# FPGA_CLKs.net
KiCad netlist of a schematic drawn in Altium Designer
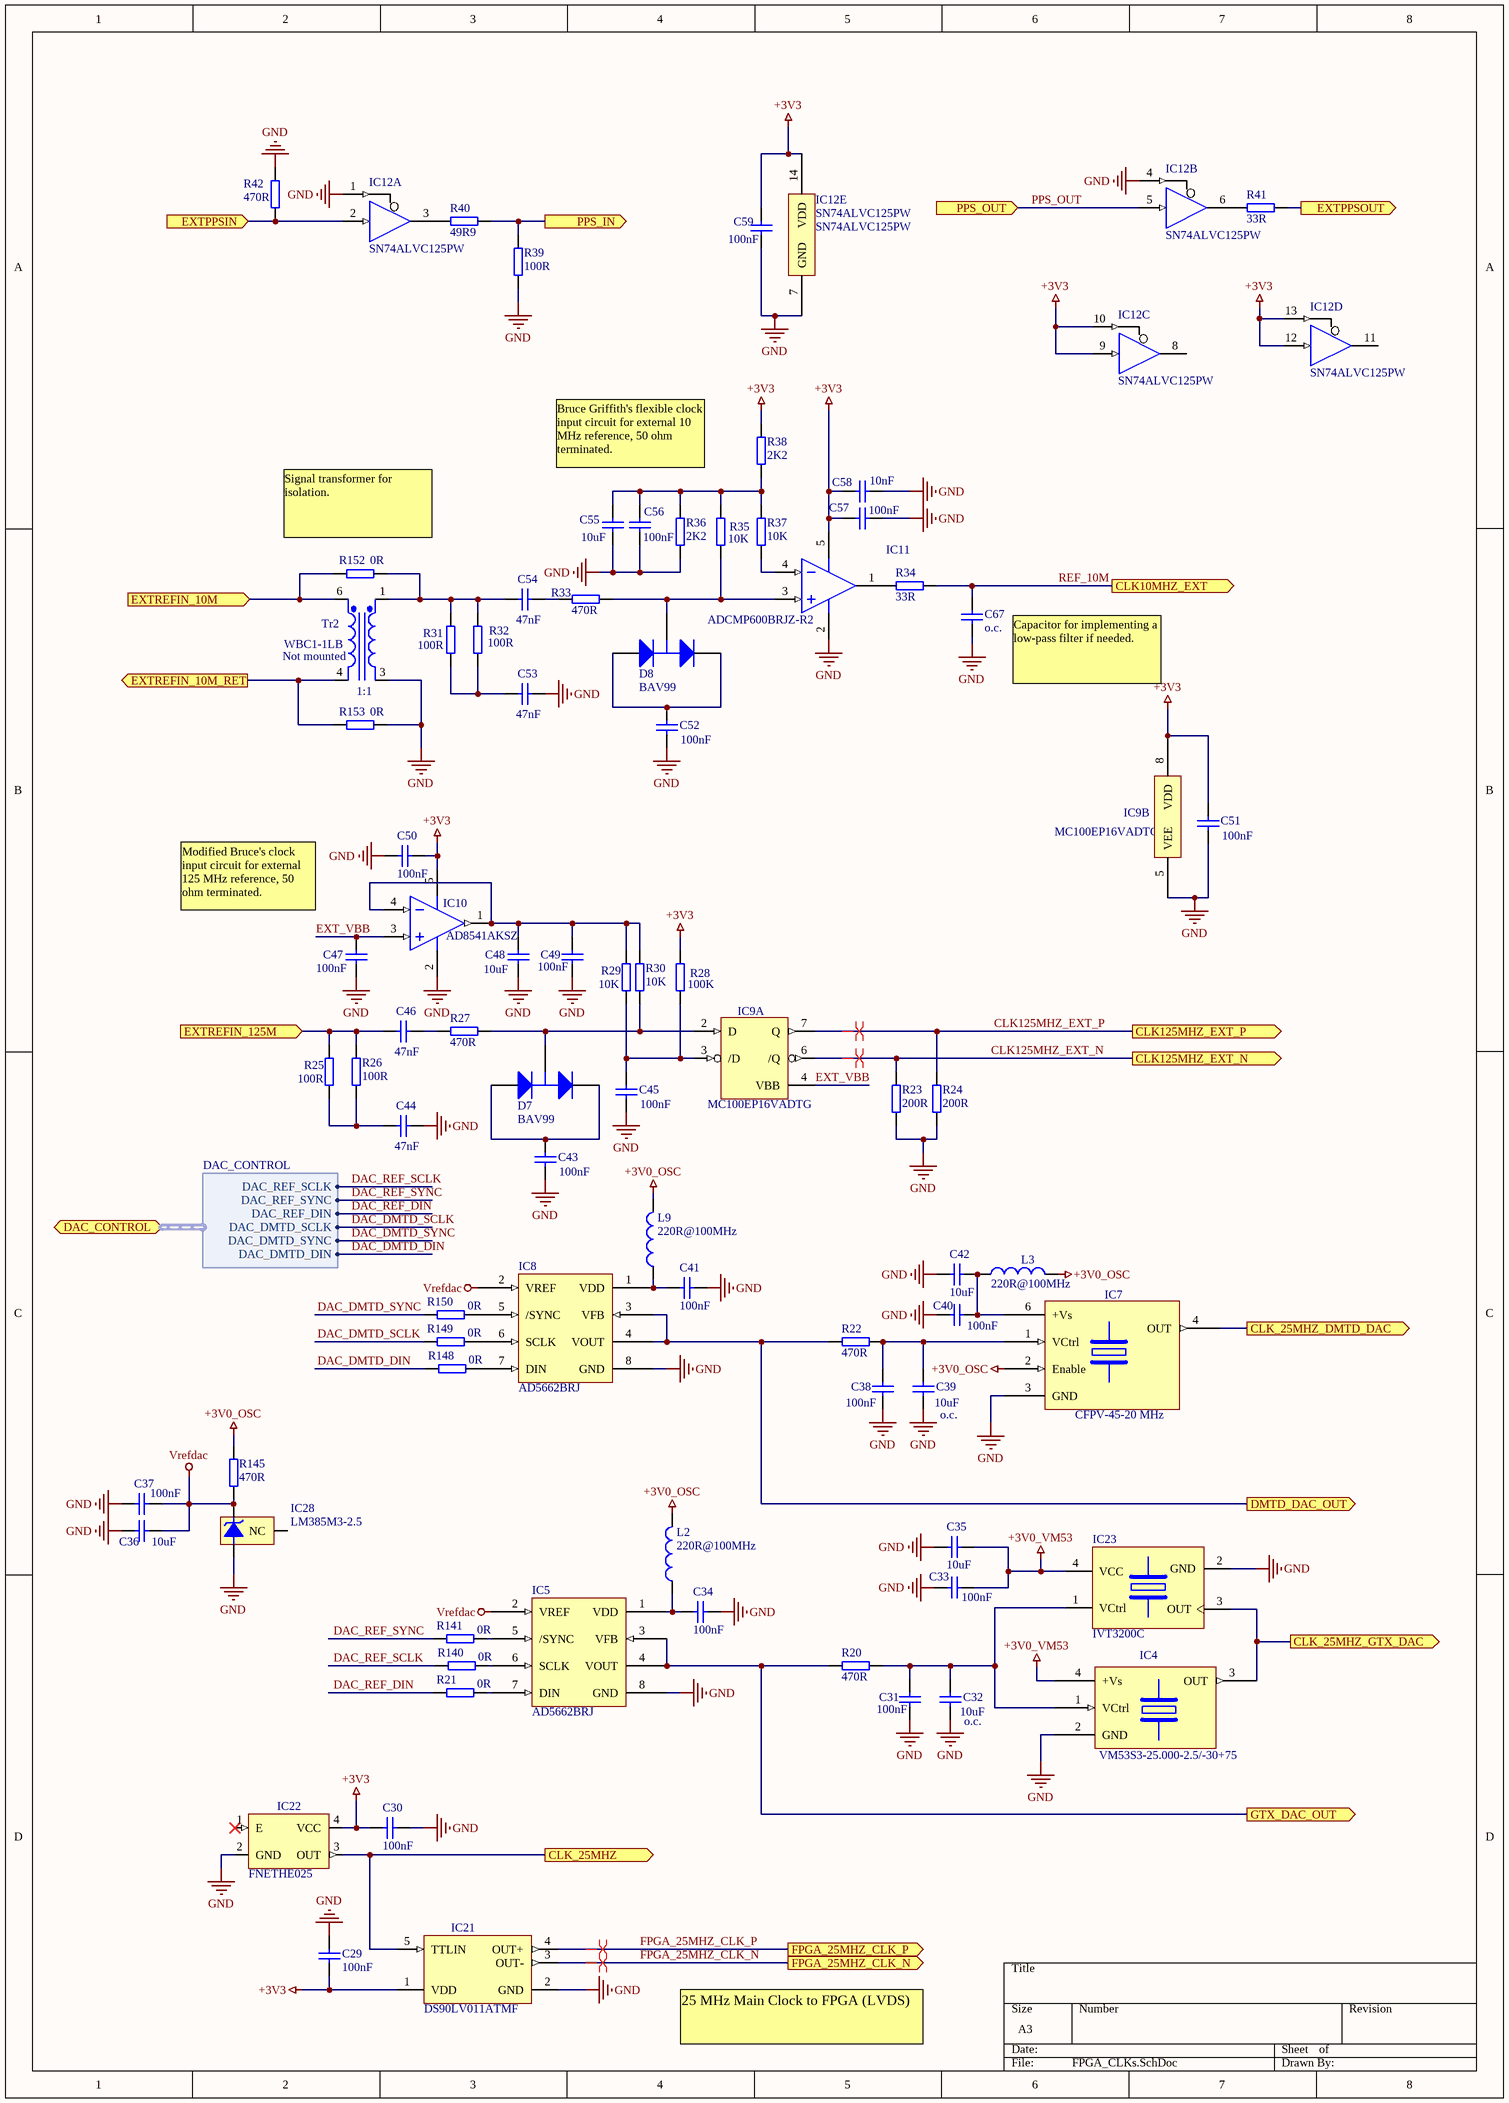
[diagram p0: FPGA_CLKs.SchDoc]

(export (version "E")
  (design (tool "Eeschema 10.0.6"))
  (components
    (comp (ref "C29")
      (value "100nF")
      (footprint "CC1005-0402")
      (description "Capacitor")
      (fields
        (field (name "TOLERANCE") "±10%")
        (field (name "VOLTAGE") "16V")
        (field (name "PUBLISHER") "Altium Limited")
      )
      (libsource (lib "wr_switch") (part "Cap"))
    )
    (comp (ref "C30")
      (value "100nF")
      (footprint "CC1005-0402")
      (description "Capacitor")
      (fields
        (field (name "TOLERANCE") "±10%")
        (field (name "VOLTAGE") "16V")
        (field (name "PUBLISHER") "Altium Limited")
      )
      (libsource (lib "wr_switch") (part "Cap"))
    )
    (comp (ref "C31")
      (value "100nF")
      (footprint "CC1005-0402")
      (description "Capacitor")
      (fields
        (field (name "TOLERANCE") "±10%")
        (field (name "VOLTAGE") "16V")
        (field (name "PUBLISHER") "Altium Limited")
      )
      (libsource (lib "wr_switch") (part "Cap"))
    )
    (comp (ref "C32")
      (value "10uF")
      (footprint "CC1608-0603")
      (description "Capacitor")
      (fields
        (field (name "TOLERANCE") "±20%")
        (field (name "VOLTAGE") "6.3V")
        (field (name "ALTIUM_VALUE") "o.c.")
        (field (name "PUBLISHER") "Altium Limited")
      )
      (libsource (lib "wr_switch") (part "Cap"))
    )
    (comp (ref "C33")
      (value "100nF")
      (footprint "CC1005-0402")
      (description "Capacitor")
      (fields
        (field (name "TOLERANCE") "±10%")
        (field (name "VOLTAGE") "16V")
        (field (name "PUBLISHER") "Altium Limited")
      )
      (libsource (lib "wr_switch") (part "Cap"))
    )
    (comp (ref "C34")
      (value "100nF")
      (footprint "CC1005-0402")
      (description "Capacitor")
      (fields
        (field (name "TOLERANCE") "±10%")
        (field (name "VOLTAGE") "16V")
        (field (name "PUBLISHER") "Altium Limited")
      )
      (libsource (lib "wr_switch") (part "Cap"))
    )
    (comp (ref "C35")
      (value "10uF")
      (footprint "CC1608-0603")
      (description "Capacitor")
      (fields
        (field (name "TOLERANCE") "±20%")
        (field (name "VOLTAGE") "6.3V")
        (field (name "PUBLISHER") "Altium Limited")
      )
      (libsource (lib "wr_switch") (part "Cap"))
    )
    (comp (ref "C36")
      (value "10uF")
      (footprint "CC1608-0603")
      (description "Capacitor")
      (fields
        (field (name "TOLERANCE") "±20%")
        (field (name "VOLTAGE") "6.3V")
        (field (name "PUBLISHER") "Altium Limited")
      )
      (libsource (lib "wr_switch") (part "Cap"))
    )
    (comp (ref "C37")
      (value "100nF")
      (footprint "CC1005-0402")
      (description "Capacitor")
      (fields
        (field (name "TOLERANCE") "±10%")
        (field (name "VOLTAGE") "16V")
        (field (name "PUBLISHER") "Altium Limited")
      )
      (libsource (lib "wr_switch") (part "Cap"))
    )
    (comp (ref "C38")
      (value "100nF")
      (footprint "CC1005-0402")
      (description "Capacitor")
      (fields
        (field (name "TOLERANCE") "±10%")
        (field (name "VOLTAGE") "16V")
        (field (name "PUBLISHER") "Altium Limited")
      )
      (libsource (lib "wr_switch") (part "Cap"))
    )
    (comp (ref "C39")
      (value "10uF")
      (footprint "CC1608-0603")
      (description "Capacitor")
      (fields
        (field (name "TOLERANCE") "±20%")
        (field (name "VOLTAGE") "6.3V")
        (field (name "ALTIUM_VALUE") "o.c.")
        (field (name "PUBLISHER") "Altium Limited")
      )
      (libsource (lib "wr_switch") (part "Cap"))
    )
    (comp (ref "C40")
      (value "100nF")
      (footprint "CC1005-0402")
      (description "Capacitor")
      (fields
        (field (name "TOLERANCE") "±10%")
        (field (name "VOLTAGE") "16V")
        (field (name "PUBLISHER") "Altium Limited")
      )
      (libsource (lib "wr_switch") (part "Cap"))
    )
    (comp (ref "C41")
      (value "100nF")
      (footprint "CC1005-0402")
      (description "Capacitor")
      (fields
        (field (name "TOLERANCE") "±10%")
        (field (name "VOLTAGE") "16V")
        (field (name "PUBLISHER") "Altium Limited")
      )
      (libsource (lib "wr_switch") (part "Cap"))
    )
    (comp (ref "C42")
      (value "10uF")
      (footprint "CC1608-0603")
      (description "Capacitor")
      (fields
        (field (name "TOLERANCE") "±20%")
        (field (name "VOLTAGE") "6.3V")
        (field (name "PUBLISHER") "Altium Limited")
      )
      (libsource (lib "wr_switch") (part "Cap"))
    )
    (comp (ref "C43")
      (value "100nF")
      (footprint "CC1005-0402")
      (description "Capacitor")
      (fields
        (field (name "TOLERANCE") "±10%")
        (field (name "VOLTAGE") "16V")
        (field (name "PUBLISHER") "Altium Limited")
      )
      (libsource (lib "wr_switch") (part "Cap"))
    )
    (comp (ref "C44")
      (value "47nF")
      (footprint "CC1005-0402")
      (description "Capacitor")
      (fields
        (field (name "TOLERANCE") "±10%")
        (field (name "VOLTAGE") "25V")
        (field (name "PUBLISHER") "Altium Limited")
      )
      (libsource (lib "wr_switch") (part "Cap"))
    )
    (comp (ref "C45")
      (value "100nF")
      (footprint "CC1005-0402")
      (description "Capacitor")
      (fields
        (field (name "TOLERANCE") "±10%")
        (field (name "VOLTAGE") "16V")
        (field (name "PUBLISHER") "Altium Limited")
      )
      (libsource (lib "wr_switch") (part "Cap"))
    )
    (comp (ref "C46")
      (value "47nF")
      (footprint "CC1005-0402")
      (description "Capacitor")
      (fields
        (field (name "TOLERANCE") "±10%")
        (field (name "VOLTAGE") "25V")
        (field (name "PUBLISHER") "Altium Limited")
      )
      (libsource (lib "wr_switch") (part "Cap"))
    )
    (comp (ref "C47")
      (value "100nF")
      (footprint "CC1005-0402")
      (description "Capacitor")
      (fields
        (field (name "TOLERANCE") "±10%")
        (field (name "VOLTAGE") "16V")
        (field (name "PUBLISHER") "Altium Limited")
      )
      (libsource (lib "wr_switch") (part "Cap"))
    )
    (comp (ref "C48")
      (value "10uF")
      (footprint "CC1608-0603")
      (description "Capacitor")
      (fields
        (field (name "TOLERANCE") "±20%")
        (field (name "VOLTAGE") "6.3V")
        (field (name "PUBLISHER") "Altium Limited")
      )
      (libsource (lib "wr_switch") (part "Cap"))
    )
    (comp (ref "C49")
      (value "100nF")
      (footprint "CC1005-0402")
      (description "Capacitor")
      (fields
        (field (name "TOLERANCE") "±10%")
        (field (name "VOLTAGE") "16V")
        (field (name "PUBLISHER") "Altium Limited")
      )
      (libsource (lib "wr_switch") (part "Cap"))
    )
    (comp (ref "C50")
      (value "100nF")
      (footprint "CC1005-0402")
      (description "Capacitor")
      (fields
        (field (name "TOLERANCE") "±10%")
        (field (name "VOLTAGE") "16V")
        (field (name "PUBLISHER") "Altium Limited")
      )
      (libsource (lib "wr_switch") (part "Cap"))
    )
    (comp (ref "C51")
      (value "100nF")
      (footprint "CC1005-0402")
      (description "Capacitor")
      (fields
        (field (name "TOLERANCE") "±10%")
        (field (name "VOLTAGE") "16V")
        (field (name "PUBLISHER") "Altium Limited")
      )
      (libsource (lib "wr_switch") (part "Cap"))
    )
    (comp (ref "C52")
      (value "100nF")
      (footprint "CC1005-0402")
      (description "Capacitor")
      (fields
        (field (name "TOLERANCE") "±10%")
        (field (name "VOLTAGE") "16V")
        (field (name "PUBLISHER") "Altium Limited")
      )
      (libsource (lib "wr_switch") (part "Cap"))
    )
    (comp (ref "C53")
      (value "47nF")
      (footprint "CC1005-0402")
      (description "Capacitor")
      (fields
        (field (name "TOLERANCE") "±10%")
        (field (name "VOLTAGE") "25V")
        (field (name "PUBLISHER") "Altium Limited")
      )
      (libsource (lib "wr_switch") (part "Cap"))
    )
    (comp (ref "C54")
      (value "47nF")
      (footprint "CC1005-0402")
      (description "Capacitor")
      (fields
        (field (name "TOLERANCE") "±10%")
        (field (name "VOLTAGE") "25V")
        (field (name "PUBLISHER") "Altium Limited")
      )
      (libsource (lib "wr_switch") (part "Cap"))
    )
    (comp (ref "C55")
      (value "10uF")
      (footprint "CC1608-0603")
      (description "Capacitor")
      (fields
        (field (name "TOLERANCE") "±20%")
        (field (name "VOLTAGE") "6.3V")
        (field (name "PUBLISHER") "Altium Limited")
      )
      (libsource (lib "wr_switch") (part "Cap"))
    )
    (comp (ref "C56")
      (value "100nF")
      (footprint "CC1005-0402")
      (description "Capacitor")
      (fields
        (field (name "TOLERANCE") "±10%")
        (field (name "VOLTAGE") "16V")
        (field (name "PUBLISHER") "Altium Limited")
      )
      (libsource (lib "wr_switch") (part "Cap"))
    )
    (comp (ref "C57")
      (value "100nF")
      (footprint "CC1005-0402")
      (description "Capacitor")
      (fields
        (field (name "TOLERANCE") "±10%")
        (field (name "VOLTAGE") "16V")
        (field (name "PUBLISHER") "Altium Limited")
      )
      (libsource (lib "wr_switch") (part "Cap"))
    )
    (comp (ref "C58")
      (value "10nF")
      (footprint "CC1005-0402")
      (description "Capacitor")
      (fields
        (field (name "TOLERANCE") "±10%")
        (field (name "VOLTAGE") "25V")
        (field (name "PUBLISHER") "Altium Limited")
      )
      (libsource (lib "wr_switch") (part "Cap"))
    )
    (comp (ref "C59")
      (value "100nF")
      (footprint "CC1005-0402")
      (description "Capacitor")
      (fields
        (field (name "TOLERANCE") "±10%")
        (field (name "VOLTAGE") "16V")
        (field (name "PUBLISHER") "Altium Limited")
      )
      (libsource (lib "wr_switch") (part "Cap"))
    )
    (comp (ref "C67")
      (value "o.c.")
      (footprint "CC1608-0603")
      (description "Capacitor")
      (fields
        (field (name "TOLERANCE") "±10%")
        (field (name "VOLTAGE") "16V")
        (field (name "PUBLISHER") "Altium Limited")
      )
      (libsource (lib "wr_switch") (part "Cap"))
    )
    (comp (ref "D7")
      (value "BAV99")
      (footprint "SOT-23")
      (description "Silicon Switching Diode Array for High-Speed Switching")
      (fields (field (name "PUBLISHER") "Altium Limited"))
      (libsource (lib "Infineon Discrete Diode") (part "BAV99"))
    )
    (comp (ref "D8")
      (value "BAV99")
      (footprint "SOT-23")
      (description "Silicon Switching Diode Array for High-Speed Switching")
      (fields (field (name "PUBLISHER") "Altium Limited"))
      (libsource (lib "Infineon Discrete Diode") (part "BAV99"))
    )
    (comp (ref "IC4")
      (value "VM53S3-25.000-2.5/-30+75")
      (footprint "VCTCXO_VM53S")
      (description "VCTCXO oscillator")
      (libsource (lib "wr_switch") (part "VCTCXO_VM53S"))
    )
    (comp (ref "IC5")
      (value "AD5662BRJ")
      (footprint "SOT23-8")
      (description "Analog Devices 16-bit DAC w/SPI interface, ext ref")
      (fields (field (name "Comment") "AD5662B"))
      (libsource (lib "wr_switch") (part "AD5662"))
    )
    (comp (ref "IC7")
      (value "CFPV-45-20 MHz")
      (footprint "vs-705")
      (description "VCXO oscillator")
      (fields (field (name "MANUFACTURER") "IQD Frequency"))
      (libsource (lib "wr_switch") (part "VCXO_CFPV_45"))
    )
    (comp (ref "IC8")
      (value "AD5662BRJ")
      (footprint "SOT23-8")
      (description "Analog Devices 16-bit DAC w/SPI interface, ext ref")
      (fields (field (name "Comment") "AD5662B"))
      (libsource (lib "wr_switch") (part "AD5662"))
    )
    (comp (ref "IC9")
      (value "MC100EP16VADTG")
      (footprint "TSOP65P490-8AN")
      (description "ONSemi differental receiver w/ECL output")
      (fields (field (name "Comment") "MC100EP16"))
      (libsource (lib "wr_switch") (part "MC100EP16"))
    )
    (comp (ref "IC10")
      (value "AD8541AKSZ")
      (footprint "SOT65P210X110-5N")
      (description "Analog Devices general purpose low-voltage R2R CMOS opamp")
      (libsource (lib "wr_switch") (part "AD8541"))
    )
    (comp (ref "IC11")
      (value "ADCMP600BRJZ-R2")
      (footprint "SOT23-5AL")
      (description "Analog Devices fast comparator")
      (libsource (lib "wr_switch") (part "ADCMP600"))
    )
    (comp (ref "IC12")
      (value "SN74ALVC125PW")
      (footprint "PW014")
      (description "Quad Buffer with 3-State Outputs with TTL Compatible Inputs")
      (fields (field (name "ALTIUM_VALUE") "SN74ALVC125PW") (field (name "Comment") "SN74ALVC125"))
      (libsource (lib "wr_switch") (part "SN74ALVC125"))
    )
    (comp (ref "IC21")
      (value "DS90LV011ATMF")
      (footprint "MF05A_N")
      (description "Single High Speed Differential Driver")
      (fields
        (field (name "MANUFACTURER") "National Semiconductor")
        (field (name "DIGIKEYPARTNUMBER") "DS90LV011ATMFTR-ND")
        (field (name "PUBLISHER") "Altium Limited")
      )
      (libsource (lib "NSC Interface") (part "DS90LV011ATMF"))
    )
    (comp (ref "IC22")
      (value "FNETHE025")
      (footprint "SPXO")
      (description "SMD oscillator 3.3V (Elfa)")
      (libsource (lib "wr_switch") (part "OSC_CFPS-73"))
    )
    (comp (ref "IC23")
      (value "IVT3200C")
      (footprint "OSC_RAKON_IVT3200C")
      (libsource (lib "wr_switch") (part "IVT32000C"))
    )
    (comp (ref "IC28")
      (value "LM385M3-2.5")
      (footprint "MF03A_N")
      (description "Micropower Voltage Reference Diode")
      (fields
        (field (name "MANUFACTURER") "National Semiconductor")
        (field (name "DIGIKEYPARTNUMBER") "LM385M3-2.5CT-ND")
        (field (name "PUBLISHER") "Altium Limited")
      )
      (libsource (lib "NSC Voltage Reference") (part "LM385M3-2.5"))
    )
    (comp (ref "L2")
      (value "220R@100MHz Ferrite Bead")
      (footprint "0603")
      (description "ferrite bead")
      (fields (field (name "IMPEDANCE") "220R@100MHz"))
      (libsource (lib "wr_switch") (part "L_FERRITE_BEAD"))
    )
    (comp (ref "L3")
      (value "220R@100MHz Ferrite Bead")
      (footprint "0603")
      (description "ferrite bead")
      (fields (field (name "IMPEDANCE") "220R@100MHz"))
      (libsource (lib "wr_switch") (part "L_FERRITE_BEAD"))
    )
    (comp (ref "L9")
      (value "220R@100MHz Ferrite Bead")
      (footprint "0603")
      (description "ferrite bead")
      (fields (field (name "IMPEDANCE") "220R@100MHz"))
      (libsource (lib "wr_switch") (part "L_FERRITE_BEAD"))
    )
    (comp (ref "R20")
      (value "470R")
      (footprint "0402")
      (description "SMD Resistor")
      (fields (field (name "TOLERANCE") "±1%"))
      (libsource (lib "wr_switch") (part "RES_SMD"))
    )
    (comp (ref "R21")
      (value "0R")
      (footprint "0603")
      (description "SMD Resistor")
      (libsource (lib "wr_switch") (part "RES_SMD"))
    )
    (comp (ref "R22")
      (value "470R")
      (footprint "0402")
      (description "SMD Resistor")
      (fields (field (name "TOLERANCE") "±1%"))
      (libsource (lib "wr_switch") (part "RES_SMD"))
    )
    (comp (ref "R23")
      (value "200R")
      (footprint "0402")
      (description "SMD Resistor")
      (fields (field (name "TOLERANCE") "±1%"))
      (libsource (lib "wr_switch") (part "RES_SMD"))
    )
    (comp (ref "R24")
      (value "200R")
      (footprint "0402")
      (description "SMD Resistor")
      (fields (field (name "TOLERANCE") "±1%"))
      (libsource (lib "wr_switch") (part "RES_SMD"))
    )
    (comp (ref "R25")
      (value "100R")
      (footprint "0402")
      (description "SMD Resistor")
      (fields (field (name "TOLERANCE") "±1%"))
      (libsource (lib "wr_switch") (part "RES_SMD"))
    )
    (comp (ref "R26")
      (value "100R")
      (footprint "0402")
      (description "SMD Resistor")
      (fields (field (name "TOLERANCE") "±1%"))
      (libsource (lib "wr_switch") (part "RES_SMD"))
    )
    (comp (ref "R27")
      (value "470R")
      (footprint "0402")
      (description "SMD Resistor")
      (fields (field (name "TOLERANCE") "±1%"))
      (libsource (lib "wr_switch") (part "RES_SMD"))
    )
    (comp (ref "R28")
      (value "100K")
      (footprint "0402")
      (description "SMD Resistor")
      (fields (field (name "TOLERANCE") "±1%"))
      (libsource (lib "wr_switch") (part "RES_SMD"))
    )
    (comp (ref "R29")
      (value "10K")
      (footprint "0402")
      (description "SMD Resistor")
      (fields (field (name "TOLERANCE") "±1%") (field (name "Comment") "10k"))
      (libsource (lib "wr_switch") (part "RES_SMD"))
    )
    (comp (ref "R30")
      (value "10K")
      (footprint "0402")
      (description "SMD Resistor")
      (fields (field (name "TOLERANCE") "±1%") (field (name "Comment") "10k"))
      (libsource (lib "wr_switch") (part "RES_SMD"))
    )
    (comp (ref "R31")
      (value "100R")
      (footprint "0402")
      (description "SMD Resistor")
      (fields (field (name "TOLERANCE") "±1%"))
      (libsource (lib "wr_switch") (part "RES_SMD"))
    )
    (comp (ref "R32")
      (value "100R")
      (footprint "0402")
      (description "SMD Resistor")
      (fields (field (name "TOLERANCE") "±1%"))
      (libsource (lib "wr_switch") (part "RES_SMD"))
    )
    (comp (ref "R33")
      (value "470R")
      (footprint "0402")
      (description "SMD Resistor")
      (fields (field (name "TOLERANCE") "±1%"))
      (libsource (lib "wr_switch") (part "RES_SMD"))
    )
    (comp (ref "R34")
      (value "33R")
      (footprint "0603")
      (description "SMD Resistor")
      (fields (field (name "TOLERANCE") "±1%"))
      (libsource (lib "wr_switch") (part "RES_SMD"))
    )
    (comp (ref "R35")
      (value "10K")
      (footprint "0402")
      (description "SMD Resistor")
      (fields (field (name "TOLERANCE") "±1%") (field (name "Comment") "10k"))
      (libsource (lib "wr_switch") (part "RES_SMD"))
    )
    (comp (ref "R36")
      (value "2K2")
      (footprint "0402")
      (description "SMD Resistor")
      (fields (field (name "TOLERANCE") "±1%"))
      (libsource (lib "wr_switch") (part "RES_SMD"))
    )
    (comp (ref "R37")
      (value "10K")
      (footprint "0402")
      (description "SMD Resistor")
      (fields (field (name "TOLERANCE") "±1%") (field (name "Comment") "10k"))
      (libsource (lib "wr_switch") (part "RES_SMD"))
    )
    (comp (ref "R38")
      (value "2K2")
      (footprint "0402")
      (description "SMD Resistor")
      (fields (field (name "TOLERANCE") "±1%"))
      (libsource (lib "wr_switch") (part "RES_SMD"))
    )
    (comp (ref "R39")
      (value "100R")
      (footprint "0402")
      (description "SMD Resistor")
      (fields (field (name "TOLERANCE") "±1%"))
      (libsource (lib "wr_switch") (part "RES_SMD"))
    )
    (comp (ref "R40")
      (value "49R9")
      (footprint "0603")
      (description "SMD Resistor")
      (fields (field (name "TOLERANCE") "±1%"))
      (libsource (lib "wr_switch") (part "RES_SMD"))
    )
    (comp (ref "R41")
      (value "33R")
      (footprint "0603")
      (description "SMD Resistor")
      (fields (field (name "TOLERANCE") "±1%"))
      (libsource (lib "wr_switch") (part "RES_SMD"))
    )
    (comp (ref "R42")
      (value "470R")
      (footprint "0402")
      (description "SMD Resistor")
      (fields (field (name "TOLERANCE") "±1%"))
      (libsource (lib "wr_switch") (part "RES_SMD"))
    )
    (comp (ref "R140")
      (value "0R")
      (footprint "0603")
      (description "SMD Resistor")
      (libsource (lib "wr_switch") (part "RES_SMD"))
    )
    (comp (ref "R141")
      (value "0R")
      (footprint "0603")
      (description "SMD Resistor")
      (libsource (lib "wr_switch") (part "RES_SMD"))
    )
    (comp (ref "R145")
      (value "470R")
      (footprint "0402")
      (description "SMD Resistor")
      (fields (field (name "TOLERANCE") "±1%"))
      (libsource (lib "wr_switch") (part "RES_SMD"))
    )
    (comp (ref "R148")
      (value "0R")
      (footprint "0603")
      (description "SMD Resistor")
      (libsource (lib "wr_switch") (part "RES_SMD"))
    )
    (comp (ref "R149")
      (value "0R")
      (footprint "0603")
      (description "SMD Resistor")
      (libsource (lib "wr_switch") (part "RES_SMD"))
    )
    (comp (ref "R150")
      (value "0R")
      (footprint "0603")
      (description "SMD Resistor")
      (libsource (lib "wr_switch") (part "RES_SMD"))
    )
    (comp (ref "R152")
      (value "0R")
      (footprint "0402")
      (description "SMD Resistor")
      (fields (field (name "TOLERANCE") "Jumper"))
      (libsource (lib "wr_switch") (part "RES_SMD"))
    )
    (comp (ref "R153")
      (value "0R")
      (footprint "0402")
      (description "SMD Resistor")
      (fields (field (name "TOLERANCE") "Jumper"))
      (libsource (lib "wr_switch") (part "RES_SMD"))
    )
    (comp (ref "Tr2")
      (value "WBC1-1LB")
      (footprint "SMT6P150P")
      (description "SMT Mini WideBand Transformer 1:1, 10uH,")
      (fields
        (field (name "MANUFACTURER") "Coilcraft")
        (field (name "ALTIUM_VALUE") "1:1")
        (field (name "MOUNTED") "Not mounted")
        (field (name "PUBLISHER") "Altium Limited")
      )
      (libsource (lib "wr_switch") (part "WBC1-1LB"))
    )
  )
  (nets
    (net (code "2") (name "+3V0_OSC") (class "Default")
      (node (ref "IC7") (pin "2") (pinfunction "Enable_2") (pintype "input"))
      (node (ref "L2") (pin "2") (pinfunction "2_2") (pintype "passive"))
      (node (ref "L3") (pin "2") (pinfunction "2_2") (pintype "passive"))
      (node (ref "L9") (pin "2") (pinfunction "2_2") (pintype "passive"))
      (node (ref "R145") (pin "2") (pinfunction "2_2") (pintype "passive"))
    )
    (net (code "3") (name "+3V0_VM53") (class "Default")
      (node (ref "C33") (pin "1") (pinfunction "1_1") (pintype "passive"))
      (node (ref "C35") (pin "1") (pinfunction "1_1") (pintype "passive"))
      (node (ref "IC23") (pin "4") (pinfunction "VCC_4") (pintype "power_in"))
      (node (ref "IC4") (pin "4") (pinfunction "+Vs_4") (pintype "power_in"))
    )
    (net (code "4") (name "+3V3") (class "Default")
      (node (ref "C29") (pin "2") (pinfunction "2_2") (pintype "passive"))
      (node (ref "C30") (pin "2") (pinfunction "2_2") (pintype "passive"))
      (node (ref "C50") (pin "1") (pinfunction "1_1") (pintype "passive"))
      (node (ref "C51") (pin "2") (pinfunction "2_2") (pintype "passive"))
      (node (ref "C57") (pin "2") (pinfunction "2_2") (pintype "passive"))
      (node (ref "C58") (pin "2") (pinfunction "2_2") (pintype "passive"))
      (node (ref "C59") (pin "2") (pinfunction "2_2") (pintype "passive"))
      (node (ref "IC10") (pin "5") (pinfunction "V+_5") (pintype "power_in"))
      (node (ref "IC11") (pin "5") (pinfunction "VCC/VCCO_5") (pintype "power_in"))
      (node (ref "IC12") (pin "10") (pinfunction "~{A}_10") (pintype "input"))
      (node (ref "IC12") (pin "12") (pinfunction "B_12") (pintype "input"))
      (node (ref "IC12") (pin "13") (pinfunction "~{A}_13") (pintype "input"))
      (node (ref "IC12") (pin "14") (pinfunction "VDD_14") (pintype "passive"))
      (node (ref "IC12") (pin "9") (pinfunction "B_9") (pintype "input"))
      (node (ref "IC21") (pin "1") (pinfunction "VDD_1") (pintype "power_in"))
      (node (ref "IC22") (pin "4") (pinfunction "VCC_4") (pintype "power_in"))
      (node (ref "IC9") (pin "8") (pinfunction "VDD_8") (pintype "passive"))
      (node (ref "R28") (pin "2") (pinfunction "2_2") (pintype "passive"))
      (node (ref "R38") (pin "2") (pinfunction "2_2") (pintype "passive"))
    )
    (net (code "5") (name "/CLK125MHZ_EXT_N") (class "Default")
      (node (ref "IC9") (pin "6") (pinfunction "/Q_6") (pintype "output"))
      (node (ref "R23") (pin "2") (pinfunction "2_2") (pintype "passive"))
    )
    (net (code "6") (name "/CLK125MHZ_EXT_P") (class "Default")
      (node (ref "IC9") (pin "7") (pinfunction "Q_7") (pintype "output"))
      (node (ref "R24") (pin "2") (pinfunction "2_2") (pintype "passive"))
    )
    (net (code "7") (name "/CLK_25MHZ") (class "Default")
      (node (ref "IC21") (pin "5") (pinfunction "TTLIN_5") (pintype "input"))
      (node (ref "IC22") (pin "3") (pinfunction "OUT_3") (pintype "output"))
    )
    (net (code "8") (name "/CLK_25MHZ_DMTD_DAC") (class "Default")
      (node (ref "IC7") (pin "4") (pinfunction "OUT_4") (pintype "output"))
    )
    (net (code "9") (name "/CLK_25MHZ_GTX_DAC") (class "Default")
      (node (ref "IC23") (pin "3") (pinfunction "OUT_3") (pintype "passive"))
      (node (ref "IC4") (pin "3") (pinfunction "OUT_3") (pintype "output"))
    )
    (net (code "10") (name "/DAC_DMTD_DIN") (class "Default")
      (node (ref "R148") (pin "2") (pinfunction "2_2") (pintype "passive"))
    )
    (net (code "11") (name "/DAC_DMTD_SCLK") (class "Default")
      (node (ref "R149") (pin "2") (pinfunction "2_2") (pintype "passive"))
    )
    (net (code "12") (name "/DAC_DMTD_SYNC") (class "Default")
      (node (ref "R150") (pin "2") (pinfunction "2_2") (pintype "passive"))
    )
    (net (code "13") (name "/DAC_REF_DIN") (class "Default")
      (node (ref "R21") (pin "2") (pinfunction "2_2") (pintype "passive"))
    )
    (net (code "14") (name "/DAC_REF_SCLK") (class "Default")
      (node (ref "R140") (pin "2") (pinfunction "2_2") (pintype "passive"))
    )
    (net (code "15") (name "/DAC_REF_SYNC") (class "Default")
      (node (ref "R141") (pin "2") (pinfunction "2_2") (pintype "passive"))
    )
    (net (code "16") (name "/DMTD_DAC_OUT") (class "Default")
      (node (ref "IC8") (pin "3") (pinfunction "VFB_3") (pintype "input"))
      (node (ref "IC8") (pin "4") (pinfunction "VOUT_4") (pintype "power_in"))
      (node (ref "R22") (pin "1") (pinfunction "1_1") (pintype "passive"))
    )
    (net (code "17") (name "/EXTPPSIN") (class "Default")
      (node (ref "IC12") (pin "2") (pinfunction "B_2") (pintype "input"))
      (node (ref "R42") (pin "1") (pinfunction "1_1") (pintype "passive"))
    )
    (net (code "18") (name "/EXTPPSOUT") (class "Default")
      (node (ref "R41") (pin "2") (pinfunction "2_2") (pintype "passive"))
    )
    (net (code "19") (name "/EXTREFIN_10M") (class "Default")
      (node (ref "R152") (pin "2") (pinfunction "2_2") (pintype "passive"))
      (node (ref "Tr2") (pin "6") (pinfunction "Pri+_6") (pintype "passive"))
    )
    (net (code "20") (name "/EXTREFIN_10M_RET") (class "Default")
      (node (ref "R153") (pin "2") (pinfunction "2_2") (pintype "passive"))
      (node (ref "Tr2") (pin "4") (pinfunction "Pri-_4") (pintype "passive"))
    )
    (net (code "21") (name "/EXTREFIN_125M") (class "Default")
      (node (ref "C46") (pin "1") (pinfunction "1_1") (pintype "passive"))
      (node (ref "R25") (pin "2") (pinfunction "2_2") (pintype "passive"))
      (node (ref "R26") (pin "2") (pinfunction "2_2") (pintype "passive"))
    )
    (net (code "22") (name "/EXT_VBB") (class "Default")
      (node (ref "C47") (pin "2") (pinfunction "2_2") (pintype "passive"))
      (node (ref "IC10") (pin "3") (pinfunction "IN+_3") (pintype "input"))
      (node (ref "IC9") (pin "4") (pinfunction "VBB_4") (pintype "passive"))
    )
    (net (code "23") (name "/FPGA_25MHZ_CLK_N") (class "Default")
      (node (ref "IC21") (pin "3") (pinfunction "OUT-_3") (pintype "output"))
    )
    (net (code "24") (name "/FPGA_25MHZ_CLK_P") (class "Default")
      (node (ref "IC21") (pin "4") (pinfunction "OUT+_4") (pintype "output"))
    )
    (net (code "25") (name "/GTX_DAC_OUT") (class "Default")
      (node (ref "IC5") (pin "3") (pinfunction "VFB_3") (pintype "input"))
      (node (ref "IC5") (pin "4") (pinfunction "VOUT_4") (pintype "power_in"))
      (node (ref "R20") (pin "1") (pinfunction "1_1") (pintype "passive"))
    )
    (net (code "26") (name "/PPS_IN") (class "Default")
      (node (ref "R39") (pin "2") (pinfunction "2_2") (pintype "passive"))
      (node (ref "R40") (pin "2") (pinfunction "2_2") (pintype "passive"))
    )
    (net (code "27") (name "/PPS_OUT") (class "Default")
      (node (ref "IC12") (pin "5") (pinfunction "B_5") (pintype "input"))
    )
    (net (code "28") (name "/REF_10M") (class "Default")
      (node (ref "C67") (pin "2") (pinfunction "2_2") (pintype "passive"))
      (node (ref "R34") (pin "2") (pinfunction "2_2") (pintype "passive"))
    )
    (net (code "30") (name "GND") (class "Default")
      (node (ref "C29") (pin "1") (pinfunction "1_1") (pintype "passive"))
      (node (ref "C30") (pin "1") (pinfunction "1_1") (pintype "passive"))
      (node (ref "C31") (pin "1") (pinfunction "1_1") (pintype "passive"))
      (node (ref "C32") (pin "1") (pinfunction "1_1") (pintype "passive"))
      (node (ref "C33") (pin "2") (pinfunction "2_2") (pintype "passive"))
      (node (ref "C34") (pin "1") (pinfunction "1_1") (pintype "passive"))
      (node (ref "C35") (pin "2") (pinfunction "2_2") (pintype "passive"))
      (node (ref "C36") (pin "1") (pinfunction "1_1") (pintype "passive"))
      (node (ref "C37") (pin "2") (pinfunction "2_2") (pintype "passive"))
      (node (ref "C38") (pin "1") (pinfunction "1_1") (pintype "passive"))
      (node (ref "C39") (pin "1") (pinfunction "1_1") (pintype "passive"))
      (node (ref "C40") (pin "2") (pinfunction "2_2") (pintype "passive"))
      (node (ref "C41") (pin "1") (pinfunction "1_1") (pintype "passive"))
      (node (ref "C42") (pin "2") (pinfunction "2_2") (pintype "passive"))
      (node (ref "C43") (pin "1") (pinfunction "1_1") (pintype "passive"))
      (node (ref "C44") (pin "2") (pinfunction "2_2") (pintype "passive"))
      (node (ref "C45") (pin "1") (pinfunction "1_1") (pintype "passive"))
      (node (ref "C47") (pin "1") (pinfunction "1_1") (pintype "passive"))
      (node (ref "C48") (pin "1") (pinfunction "1_1") (pintype "passive"))
      (node (ref "C49") (pin "1") (pinfunction "1_1") (pintype "passive"))
      (node (ref "C50") (pin "2") (pinfunction "2_2") (pintype "passive"))
      (node (ref "C51") (pin "1") (pinfunction "1_1") (pintype "passive"))
      (node (ref "C52") (pin "1") (pinfunction "1_1") (pintype "passive"))
      (node (ref "C53") (pin "2") (pinfunction "2_2") (pintype "passive"))
      (node (ref "C55") (pin "1") (pinfunction "1_1") (pintype "passive"))
      (node (ref "C56") (pin "1") (pinfunction "1_1") (pintype "passive"))
      (node (ref "C57") (pin "1") (pinfunction "1_1") (pintype "passive"))
      (node (ref "C58") (pin "1") (pinfunction "1_1") (pintype "passive"))
      (node (ref "C59") (pin "1") (pinfunction "1_1") (pintype "passive"))
      (node (ref "C67") (pin "1") (pinfunction "1_1") (pintype "passive"))
      (node (ref "IC10") (pin "2") (pinfunction "V-_2") (pintype "power_in"))
      (node (ref "IC11") (pin "2") (pinfunction "VEE_2") (pintype "power_in"))
      (node (ref "IC12") (pin "1") (pinfunction "~{A}_1") (pintype "input"))
      (node (ref "IC12") (pin "4") (pinfunction "~{A}_4") (pintype "input"))
      (node (ref "IC12") (pin "7") (pinfunction "GND_7") (pintype "passive"))
      (node (ref "IC21") (pin "2") (pinfunction "GND_2") (pintype "power_in"))
      (node (ref "IC22") (pin "2") (pinfunction "GND_2") (pintype "power_in"))
      (node (ref "IC23") (pin "2") (pinfunction "GND_2") (pintype "power_in"))
      (node (ref "IC28") (pin "2") (pinfunction "-V_2") (pintype "passive"))
      (node (ref "IC4") (pin "2") (pinfunction "GND_2") (pintype "power_in"))
      (node (ref "IC5") (pin "8") (pinfunction "GND_8") (pintype "power_in"))
      (node (ref "IC7") (pin "3") (pinfunction "GND_3") (pintype "power_in"))
      (node (ref "IC8") (pin "8") (pinfunction "GND_8") (pintype "power_in"))
      (node (ref "IC9") (pin "5") (pinfunction "VEE_5") (pintype "passive"))
      (node (ref "R153") (pin "1") (pinfunction "1_1") (pintype "passive"))
      (node (ref "R23") (pin "1") (pinfunction "1_1") (pintype "passive"))
      (node (ref "R24") (pin "1") (pinfunction "1_1") (pintype "passive"))
      (node (ref "R36") (pin "1") (pinfunction "1_1") (pintype "passive"))
      (node (ref "R39") (pin "1") (pinfunction "1_1") (pintype "passive"))
      (node (ref "R42") (pin "2") (pinfunction "2_2") (pintype "passive"))
      (node (ref "Tr2") (pin "3") (pinfunction "Sec-_3") (pintype "passive"))
    )
    (net (code "31") (name "Net-(C44-Pad1)") (class "Default")
      (node (ref "C44") (pin "1") (pinfunction "1_1") (pintype "passive"))
      (node (ref "R25") (pin "1") (pinfunction "1_1") (pintype "passive"))
      (node (ref "R26") (pin "1") (pinfunction "1_1") (pintype "passive"))
    )
    (net (code "32") (name "Net-(C46-Pad2)") (class "Default")
      (node (ref "C46") (pin "2") (pinfunction "2_2") (pintype "passive"))
      (node (ref "R27") (pin "1") (pinfunction "1_1") (pintype "passive"))
    )
    (net (code "33") (name "Net-(C53-Pad1)") (class "Default")
      (node (ref "C53") (pin "1") (pinfunction "1_1") (pintype "passive"))
      (node (ref "R31") (pin "1") (pinfunction "1_1") (pintype "passive"))
      (node (ref "R32") (pin "1") (pinfunction "1_1") (pintype "passive"))
    )
    (net (code "34") (name "Net-(C54-Pad2)") (class "Default")
      (node (ref "C54") (pin "2") (pinfunction "2_2") (pintype "passive"))
      (node (ref "R33") (pin "1") (pinfunction "1_1") (pintype "passive"))
    )
    (net (code "35") (name "Net-(C55-Pad2)") (class "Default")
      (node (ref "C55") (pin "2") (pinfunction "2_2") (pintype "passive"))
      (node (ref "C56") (pin "2") (pinfunction "2_2") (pintype "passive"))
      (node (ref "R35") (pin "2") (pinfunction "2_2") (pintype "passive"))
      (node (ref "R36") (pin "2") (pinfunction "2_2") (pintype "passive"))
      (node (ref "R37") (pin "2") (pinfunction "2_2") (pintype "passive"))
      (node (ref "R38") (pin "1") (pinfunction "1_1") (pintype "passive"))
    )
    (net (code "36") (name "Net-(D7-A)") (class "Default")
      (node (ref "C43") (pin "2") (pinfunction "2_2") (pintype "passive"))
      (node (ref "D7") (pin "1") (pinfunction "A_1") (pintype "passive"))
      (node (ref "D7") (pin "2") (pinfunction "K_2") (pintype "passive"))
    )
    (net (code "37") (name "Net-(D7-C)") (class "Default")
      (node (ref "D7") (pin "3") (pinfunction "C_3") (pintype "passive"))
      (node (ref "IC9") (pin "2") (pinfunction "D_2") (pintype "input"))
      (node (ref "R27") (pin "2") (pinfunction "2_2") (pintype "passive"))
      (node (ref "R30") (pin "1") (pinfunction "1_1") (pintype "passive"))
    )
    (net (code "38") (name "Net-(D8-A)") (class "Default")
      (node (ref "C52") (pin "2") (pinfunction "2_2") (pintype "passive"))
      (node (ref "D8") (pin "1") (pinfunction "A_1") (pintype "passive"))
      (node (ref "D8") (pin "2") (pinfunction "K_2") (pintype "passive"))
    )
    (net (code "39") (name "Net-(D8-C)") (class "Default")
      (node (ref "D8") (pin "3") (pinfunction "C_3") (pintype "passive"))
      (node (ref "IC11") (pin "3") (pinfunction "VP_3") (pintype "input"))
      (node (ref "R33") (pin "2") (pinfunction "2_2") (pintype "passive"))
      (node (ref "R35") (pin "1") (pinfunction "1_1") (pintype "passive"))
    )
    (net (code "40") (name "Net-(IC5-DIN)") (class "Default")
      (node (ref "IC5") (pin "7") (pinfunction "DIN_7") (pintype "input"))
      (node (ref "R21") (pin "1") (pinfunction "1_1") (pintype "passive"))
    )
    (net (code "41") (name "Net-(IC5-SCLK)") (class "Default")
      (node (ref "IC5") (pin "6") (pinfunction "SCLK_6") (pintype "input"))
      (node (ref "R140") (pin "1") (pinfunction "1_1") (pintype "passive"))
    )
    (net (code "42") (name "Net-(IC5-VDD)") (class "Default")
      (node (ref "C34") (pin "2") (pinfunction "2_2") (pintype "passive"))
      (node (ref "IC5") (pin "1") (pinfunction "VDD_1") (pintype "power_in"))
      (node (ref "L2") (pin "1") (pinfunction "1_1") (pintype "passive"))
    )
    (net (code "43") (name "Net-(IC5-{slash}SYNC)") (class "Default")
      (node (ref "IC5") (pin "5") (pinfunction "/SYNC_5") (pintype "input"))
      (node (ref "R141") (pin "1") (pinfunction "1_1") (pintype "passive"))
    )
    (net (code "44") (name "Net-(IC7-+Vs)") (class "Default")
      (node (ref "C40") (pin "1") (pinfunction "1_1") (pintype "passive"))
      (node (ref "C42") (pin "1") (pinfunction "1_1") (pintype "passive"))
      (node (ref "IC7") (pin "6") (pinfunction "+Vs_6") (pintype "power_in"))
      (node (ref "L3") (pin "1") (pinfunction "1_1") (pintype "passive"))
    )
    (net (code "45") (name "Net-(IC7-VCtrl)") (class "Default")
      (node (ref "C38") (pin "2") (pinfunction "2_2") (pintype "passive"))
      (node (ref "C39") (pin "2") (pinfunction "2_2") (pintype "passive"))
      (node (ref "IC7") (pin "1") (pinfunction "VCtrl_1") (pintype "input"))
      (node (ref "R22") (pin "2") (pinfunction "2_2") (pintype "passive"))
    )
    (net (code "46") (name "Net-(IC8-DIN)") (class "Default")
      (node (ref "IC8") (pin "7") (pinfunction "DIN_7") (pintype "input"))
      (node (ref "R148") (pin "1") (pinfunction "1_1") (pintype "passive"))
    )
    (net (code "47") (name "Net-(IC8-SCLK)") (class "Default")
      (node (ref "IC8") (pin "6") (pinfunction "SCLK_6") (pintype "input"))
      (node (ref "R149") (pin "1") (pinfunction "1_1") (pintype "passive"))
    )
    (net (code "48") (name "Net-(IC8-VDD)") (class "Default")
      (node (ref "C41") (pin "2") (pinfunction "2_2") (pintype "passive"))
      (node (ref "IC8") (pin "1") (pinfunction "VDD_1") (pintype "power_in"))
      (node (ref "L9") (pin "1") (pinfunction "1_1") (pintype "passive"))
    )
    (net (code "49") (name "Net-(IC8-{slash}SYNC)") (class "Default")
      (node (ref "IC8") (pin "5") (pinfunction "/SYNC_5") (pintype "input"))
      (node (ref "R150") (pin "1") (pinfunction "1_1") (pintype "passive"))
    )
    (net (code "50") (name "Net-(IC9A-{slash}D)") (class "Default")
      (node (ref "C45") (pin "2") (pinfunction "2_2") (pintype "passive"))
      (node (ref "IC9") (pin "3") (pinfunction "/D_3") (pintype "input"))
      (node (ref "R28") (pin "1") (pinfunction "1_1") (pintype "passive"))
      (node (ref "R29") (pin "1") (pinfunction "1_1") (pintype "passive"))
    )
    (net (code "51") (name "Net-(IC10-IN-)") (class "Default")
      (node (ref "C48") (pin "2") (pinfunction "2_2") (pintype "passive"))
      (node (ref "C49") (pin "2") (pinfunction "2_2") (pintype "passive"))
      (node (ref "IC10") (pin "1") (pinfunction "OUT_1") (pintype "output"))
      (node (ref "IC10") (pin "4") (pinfunction "IN-_4") (pintype "input"))
      (node (ref "R29") (pin "2") (pinfunction "2_2") (pintype "passive"))
      (node (ref "R30") (pin "2") (pinfunction "2_2") (pintype "passive"))
    )
    (net (code "52") (name "Net-(IC11-Q)") (class "Default")
      (node (ref "IC11") (pin "1") (pinfunction "Q_1") (pintype "open_collector"))
      (node (ref "R34") (pin "1") (pinfunction "1_1") (pintype "passive"))
    )
    (net (code "53") (name "Net-(IC11-VN)") (class "Default")
      (node (ref "IC11") (pin "4") (pinfunction "VN_4") (pintype "input"))
      (node (ref "R37") (pin "1") (pinfunction "1_1") (pintype "passive"))
    )
    (net (code "54") (name "Net-(IC12A-Y)") (class "Default")
      (node (ref "IC12") (pin "3") (pinfunction "Y_3") (pintype "tri_state"))
      (node (ref "R40") (pin "1") (pinfunction "1_1") (pintype "passive"))
    )
    (net (code "55") (name "Net-(IC12B-Y)") (class "Default")
      (node (ref "IC12") (pin "6") (pinfunction "Y_6") (pintype "tri_state"))
      (node (ref "R41") (pin "1") (pinfunction "1_1") (pintype "passive"))
    )
    (net (code "56") (name "Net-(IC23-VCtrl)") (class "Default")
      (node (ref "C31") (pin "2") (pinfunction "2_2") (pintype "passive"))
      (node (ref "C32") (pin "2") (pinfunction "2_2") (pintype "passive"))
      (node (ref "IC23") (pin "1") (pinfunction "VCtrl_1") (pintype "passive"))
      (node (ref "IC4") (pin "1") (pinfunction "VCtrl_1") (pintype "input"))
      (node (ref "R20") (pin "2") (pinfunction "2_2") (pintype "passive"))
    )
    (net (code "57") (name "Net-(Tr2-Sec+)") (class "Default")
      (node (ref "C54") (pin "1") (pinfunction "1_1") (pintype "passive"))
      (node (ref "R152") (pin "1") (pinfunction "1_1") (pintype "passive"))
      (node (ref "R31") (pin "2") (pinfunction "2_2") (pintype "passive"))
      (node (ref "R32") (pin "2") (pinfunction "2_2") (pintype "passive"))
      (node (ref "Tr2") (pin "1") (pinfunction "Sec+_1") (pintype "passive"))
    )
    (net (code "58") (name "Vrefdac") (class "Default")
      (node (ref "C36") (pin "2") (pinfunction "2_2") (pintype "passive"))
      (node (ref "C37") (pin "1") (pinfunction "1_1") (pintype "passive"))
      (node (ref "IC28") (pin "1") (pinfunction "+V_1") (pintype "passive"))
      (node (ref "IC5") (pin "2") (pinfunction "VREF_2") (pintype "input"))
      (node (ref "IC8") (pin "2") (pinfunction "VREF_2") (pintype "input"))
      (node (ref "R145") (pin "1") (pinfunction "1_1") (pintype "passive"))
    )
    (net (code "59") (name "unconnected-(IC12C-Y-Pad8)") (class "Default")
      (node (ref "IC12") (pin "8") (pinfunction "Y_8") (pintype "tri_state"))
    )
    (net (code "60") (name "unconnected-(IC12D-Y-Pad11)") (class "Default")
      (node (ref "IC12") (pin "11") (pinfunction "Y_11") (pintype "tri_state"))
    )
    (net (code "61") (name "unconnected-(IC22-E-Pad1)") (class "Default")
      (node (ref "IC22") (pin "1") (pinfunction "E_1") (pintype "input+no_connect"))
    )
    (net (code "62") (name "unconnected-(IC28-NC-Pad3)") (class "Default")
      (node (ref "IC28") (pin "3") (pinfunction "NC_3") (pintype "passive"))
    )
  )
)
